# F030K6T6.net
KiCad netlist of a schematic drawn in Altium Designer
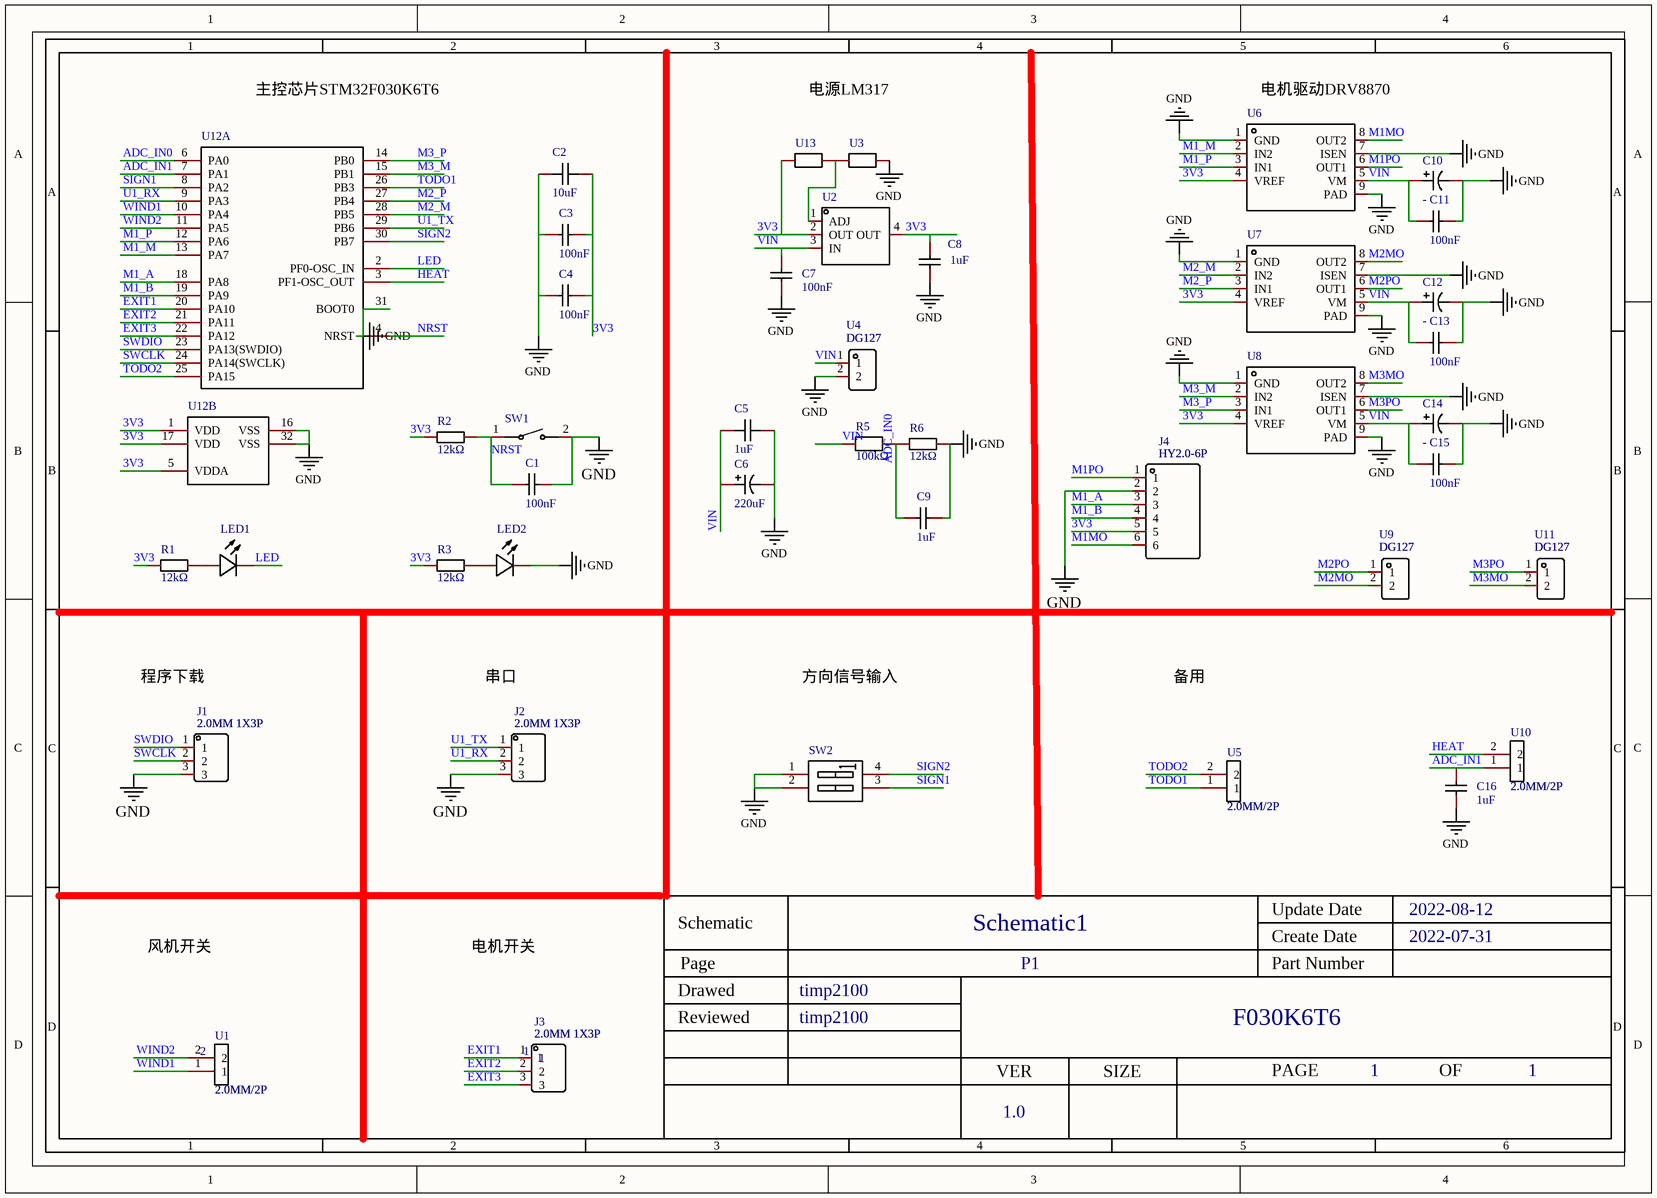
[diagram p0: F030K6T6.schdoc]

(export (version "E")
  (design (tool "Eeschema 10.0.6"))
  (components
    (comp (ref "C1")
      (value "100nF")
      (description "容值:100nF;精度:±20%;额定电压:50V;温度系数:Y5V;")
      (fields (field (name "MANUFACTURER") "FH(风华)") (field (name "MANUFACTURER PART") "0402F104M500NT"))
      (libsource (lib "altium-import") (part "root_0_0402F104M500NT_"))
    )
    (comp (ref "C2")
      (value "10uF")
      (description "容值:10uF;精度:±20%;额定电压:-;温度系数:-;")
      (fields
        (field (name "MANUFACTURER") "muRata(村田)")
        (field (name "MANUFACTURER PART") "GRJ155R60J106ME11D")
      )
      (libsource (lib "altium-import") (part "root_0_GRJ155R60J106ME11D_"))
    )
    (comp (ref "C3")
      (value "100nF")
      (description "容值:100nF;精度:±20%;额定电压:50V;温度系数:Y5V;")
      (fields (field (name "MANUFACTURER") "FH(风华)") (field (name "MANUFACTURER PART") "0402F104M500NT"))
      (libsource (lib "altium-import") (part "root_0_0402F104M500NT_"))
    )
    (comp (ref "C4")
      (value "100nF")
      (description "容值:100nF;精度:±20%;额定电压:50V;温度系数:Y5V;")
      (fields (field (name "MANUFACTURER") "FH(风华)") (field (name "MANUFACTURER PART") "0402F104M500NT"))
      (libsource (lib "altium-import") (part "root_0_0402F104M500NT_"))
    )
    (comp (ref "C5")
      (value "1uF")
      (description "容值:1uF;精度:±10%;额定电压:50V;温度系数:X5R;")
      (fields
        (field (name "MANUFACTURER") "muRata(村田)")
        (field (name "MANUFACTURER PART") "GRT188R61H105KE13D")
      )
      (libsource (lib "altium-import") (part "root_0_GRT188R61H105KE13D_"))
    )
    (comp (ref "C6")
      (value "220uF")
      (description "容值:220uF;额定电压:50V;工作寿命:2000hrs@105;")
      (fields
        (field (name "MANUFACTURER") "KNSCHA(科尼盛)")
        (field (name "MANUFACTURER PART") "RVT220UF50V67RV0021")
      )
      (libsource (lib "altium-import") (part "root_0_RVT220UF50V67RV0021_"))
    )
    (comp (ref "C7")
      (value "100nF")
      (description "容值:100nF;精度:±20%;额定电压:50V;温度系数:Y5V;")
      (fields (field (name "MANUFACTURER") "FH(风华)") (field (name "MANUFACTURER PART") "0402F104M500NT"))
      (libsource (lib "altium-import") (part "root_1_0402F104M500NT_"))
    )
    (comp (ref "C8")
      (value "1uF")
      (description "容值:1uF;精度:±10%;额定电压:10V;温度系数:X5R;")
      (fields
        (field (name "MANUFACTURER") "TAIYO YUDEN(太诱)")
        (field (name "MANUFACTURER PART") "LMK105BJ105KV-F")
      )
      (libsource (lib "altium-import") (part "root_1_LMK105BJ105KV-F_"))
    )
    (comp (ref "C9")
      (value "1uF")
      (description "容值:1uF;精度:±10%;额定电压:10V;温度系数:X5R;")
      (fields
        (field (name "MANUFACTURER") "TAIYO YUDEN(太诱)")
        (field (name "MANUFACTURER PART") "LMK105BJ105KV-F")
      )
      (libsource (lib "altium-import") (part "root_2_LMK105BJ105KV-F_"))
    )
    (comp (ref "C10")
      (value "-")
      (description "容值:-;精度:-;额定电压:-;电容体直径:-;电容体长度:-;纹波电流:-;等效串联电阻:-;工作寿命:-;工作温度:-;")
      (fields
        (field (name "MANUFACTURER") "KNSCHA(科尼盛)")
        (field (name "MANUFACTURER PART") "XT47UF50V90RV0082")
      )
      (libsource (lib "altium-import") (part "root_0_XT47UF50V90RV0082_"))
    )
    (comp (ref "C11")
      (value "100nF")
      (description "容值:100nF;精度:±20%;额定电压:50V;温度系数:Y5V;")
      (fields (field (name "MANUFACTURER") "FH(风华)") (field (name "MANUFACTURER PART") "0402F104M500NT"))
      (libsource (lib "altium-import") (part "root_0_0402F104M500NT_"))
    )
    (comp (ref "C12")
      (value "-")
      (description "容值:-;精度:-;额定电压:-;电容体直径:-;电容体长度:-;纹波电流:-;等效串联电阻:-;工作寿命:-;工作温度:-;")
      (fields
        (field (name "MANUFACTURER") "KNSCHA(科尼盛)")
        (field (name "MANUFACTURER PART") "XT47UF50V90RV0082")
      )
      (libsource (lib "altium-import") (part "root_0_XT47UF50V90RV0082_"))
    )
    (comp (ref "C13")
      (value "100nF")
      (description "容值:100nF;精度:±20%;额定电压:50V;温度系数:Y5V;")
      (fields (field (name "MANUFACTURER") "FH(风华)") (field (name "MANUFACTURER PART") "0402F104M500NT"))
      (libsource (lib "altium-import") (part "root_0_0402F104M500NT_"))
    )
    (comp (ref "C14")
      (value "-")
      (description "容值:-;精度:-;额定电压:-;电容体直径:-;电容体长度:-;纹波电流:-;等效串联电阻:-;工作寿命:-;工作温度:-;")
      (fields
        (field (name "MANUFACTURER") "KNSCHA(科尼盛)")
        (field (name "MANUFACTURER PART") "XT47UF50V90RV0082")
      )
      (libsource (lib "altium-import") (part "root_0_XT47UF50V90RV0082_"))
    )
    (comp (ref "C15")
      (value "100nF")
      (description "容值:100nF;精度:±20%;额定电压:50V;温度系数:Y5V;")
      (fields (field (name "MANUFACTURER") "FH(风华)") (field (name "MANUFACTURER PART") "0402F104M500NT"))
      (libsource (lib "altium-import") (part "root_0_0402F104M500NT_"))
    )
    (comp (ref "C16")
      (value "1uF")
      (description "容值:1uF;精度:±10%;额定电压:10V;温度系数:X5R;")
      (fields
        (field (name "MANUFACTURER") "TAIYO YUDEN(太诱)")
        (field (name "MANUFACTURER PART") "LMK105BJ105KV-F")
      )
      (libsource (lib "altium-import") (part "root_3_LMK105BJ105KV-F_"))
    )
    (comp (ref "J1")
      (value "2.0MM 1X3P")
      (fields (field (name "NAME") "2.0MM 1X3P"))
      (libsource (lib "altium-import") (part "root_0_2.0MM 1X3P_"))
    )
    (comp (ref "J2")
      (value "2.0MM 1X3P")
      (fields (field (name "NAME") "2.0MM 1X3P"))
      (libsource (lib "altium-import") (part "root_0_2.0MM 1X3P_"))
    )
    (comp (ref "J3")
      (value "2.0MM 1X3P")
      (fields (field (name "NAME") "2.0MM 1X3P") (field (name "NAME_1") "1") (field (name "NUMBER") "1"))
      (libsource (lib "altium-import") (part "root_0_2.0MM 1X3P_"))
    )
    (comp (ref "J4")
      (value "HY2.0-6P")
      (fields (field (name "NAME") "HY2.0-6P"))
      (libsource (lib "altium-import") (part "root_0_HY2.0-6P_"))
    )
    (comp (ref "LED1")
      (value "MHT136CRCT")
      (fields (field (name "MANUFACTURER") "MEIHUA(美华科技)"))
      (libsource (lib "altium-import") (part "root_0_mirrored_MHT136CRCT_"))
    )
    (comp (ref "LED2")
      (value "MHT136CGCT")
      (fields (field (name "MANUFACTURER") "MEIHUA(美华科技)"))
      (libsource (lib "altium-import") (part "root_0_mirrored_MHT136CGCT_"))
    )
    (comp (ref "R1")
      (value "12kΩ")
      (description "电阻类型:厚膜电阻;阻值:12kΩ;精度:±5%;功率:1/16W;温度系数:±100ppm/;最大工作电压:50V;工作温度范围:-55~+155;")
      (fields
        (field (name "MANUFACTURER") "UNI-ROYAL(厚声)")
        (field (name "MANUFACTURER PART") "0402WGJ0123TCE")
      )
      (libsource (lib "altium-import") (part "root_0_0402WGJ0123TCE_"))
    )
    (comp (ref "R2")
      (value "12kΩ")
      (description "电阻类型:厚膜电阻;阻值:12kΩ;精度:±5%;功率:1/16W;温度系数:±100ppm/;最大工作电压:50V;工作温度范围:-55~+155;")
      (fields
        (field (name "MANUFACTURER") "UNI-ROYAL(厚声)")
        (field (name "MANUFACTURER PART") "0402WGJ0123TCE")
      )
      (libsource (lib "altium-import") (part "root_0_0402WGJ0123TCE_"))
    )
    (comp (ref "R3")
      (value "12kΩ")
      (description "电阻类型:厚膜电阻;阻值:12kΩ;精度:±5%;功率:1/16W;温度系数:±100ppm/;最大工作电压:50V;工作温度范围:-55~+155;")
      (fields
        (field (name "MANUFACTURER") "UNI-ROYAL(厚声)")
        (field (name "MANUFACTURER PART") "0402WGJ0123TCE")
      )
      (libsource (lib "altium-import") (part "root_0_0402WGJ0123TCE_"))
    )
    (comp (ref "R5")
      (value "100kΩ")
      (description "电阻类型:薄膜电阻;阻值:100kΩ;精度:±0.25%;功率:62.5mW;温度系数:±50ppm/;最大工作电压:50V;工作温度范围:-55~+155;")
      (fields (field (name "MANUFACTURER") "YAGEO(国巨)") (field (name "MANUFACTURER PART") "RT0402CRE07100KL"))
      (libsource (lib "altium-import") (part "root_0_RT0402CRE07100KL_"))
    )
    (comp (ref "R6")
      (value "12kΩ")
      (description "电阻类型:厚膜电阻;阻值:12kΩ;精度:±5%;功率:1/16W;温度系数:±100ppm/;最大工作电压:50V;工作温度范围:-55~+155;")
      (fields
        (field (name "MANUFACTURER") "UNI-ROYAL(厚声)")
        (field (name "MANUFACTURER PART") "0402WGJ0123TCE")
      )
      (libsource (lib "altium-import") (part "root_0_0402WGJ0123TCE_"))
    )
    (comp (ref "SW1")
      (value "K2-1107ST-A4DW-06")
      (fields (field (name "MANUFACTURER") "韩国韩荣"))
      (libsource (lib "altium-import") (part "root_0_K2-1107ST-A4DW-06_"))
    )
    (comp (ref "SW2")
      (value "DS-02RP")
      (description "类型:平拨，凸起式;额定电流:25mA;额定电压:24V;电路结构:单刀单掷;开关位数:2;引脚间距:2.54mm;工作温度:-20~+70;使用寿命:3000;颜色:红色;")
      (fields (field (name "MANUFACTURER") "韩国韩荣"))
      (libsource (lib "altium-import") (part "root_0_DS-02RP_"))
    )
    (comp (ref "U1")
      (value "2.0MM/2P")
      (fields (field (name "NAME") "2.0MM/2P") (field (name "NUMBER") "2"))
      (libsource (lib "altium-import") (part "root_0_mirrored_2.0MM/2P_"))
    )
    (comp (ref "U2")
      (value "LM317")
      (description "输出类型:可调;输出极性:正;输出通道数:1;最大输入电压:40V;输出电压:1.2V~37V;压差:5V@(500mA);输出电流:1.5A;")
      (fields (field (name "MANUFACTURER") "CJ（江苏长电/长晶）"))
      (libsource (lib "altium-import") (part "root_0_LM317_"))
    )
    (comp (ref "U3")
      (value "SCR0402J20K")
      (fields (field (name "MANUFACTURER") "VO(翔胜)"))
      (libsource (lib "altium-import") (part "root_0_SCR0402J20K_"))
    )
    (comp (ref "U4")
      (value "DG127")
      (fields
        (field (name "NAME") "DG127")
        (field (name "MANUFACTURER") "DEGSON")
        (field (name "MANUFACTURER PART") "DG127-5.0-02P-14-1002A(H)")
      )
      (libsource (lib "altium-import") (part "root_0_DG127-5.0-02P-14-1002A(H)_"))
    )
    (comp (ref "U5")
      (value "2.0MM/2P")
      (fields (field (name "NAME") "2.0MM/2P"))
      (libsource (lib "altium-import") (part "root_0_mirrored_2.0MM/2P_"))
    )
    (comp (ref "U6")
      (value "DRV8870DDAR")
      (description "DRV8870 DRV8870 预售")
      (fields (field (name "MANUFACTURER") "TI(德州仪器)"))
      (libsource (lib "altium-import") (part "root_0_DRV8870DDAR_"))
    )
    (comp (ref "U7")
      (value "DRV8870DDAR")
      (description "DRV8870 DRV8870 预售")
      (fields (field (name "MANUFACTURER") "TI(德州仪器)"))
      (libsource (lib "altium-import") (part "root_0_DRV8870DDAR_"))
    )
    (comp (ref "U8")
      (value "DRV8870DDAR")
      (description "DRV8870 DRV8870 预售")
      (fields (field (name "MANUFACTURER") "TI(德州仪器)"))
      (libsource (lib "altium-import") (part "root_0_DRV8870DDAR_"))
    )
    (comp (ref "U9")
      (value "DG127")
      (fields
        (field (name "NAME") "DG127")
        (field (name "MANUFACTURER") "DEGSON")
        (field (name "MANUFACTURER PART") "DG127-5.0-02P-14-1002A(H)")
      )
      (libsource (lib "altium-import") (part "root_0_DG127-5.0-02P-14-1002A(H)_"))
    )
    (comp (ref "U10")
      (value "2.0MM/2P")
      (fields (field (name "NAME") "2.0MM/2P"))
      (libsource (lib "altium-import") (part "root_0_mirrored_2.0MM/2P_"))
    )
    (comp (ref "U11")
      (value "DG127")
      (fields
        (field (name "NAME") "DG127")
        (field (name "MANUFACTURER") "DEGSON")
        (field (name "MANUFACTURER PART") "DG127-5.0-02P-14-1002A(H)")
      )
      (libsource (lib "altium-import") (part "root_0_DG127-5.0-02P-14-1002A(H)_"))
    )
    (comp (ref "U12")
      (value "STM32F030K6T6TR")
      (description "CPU位数:-;ROM类型:-;CPU内核:-;主频（MAX):-;工作电压:-;")
      (fields (field (name "MANUFACTURER") "ST(意法半导体)"))
      (libsource (lib "altium-import") (part "root_0_STM32F030K6T6TR_"))
    )
    (comp (ref "U13")
      (value "SCR0402J20K")
      (fields (field (name "MANUFACTURER") "VO(翔胜)"))
      (libsource (lib "altium-import") (part "root_0_SCR0402J20K_"))
    )
  )
  (nets
    (net (code "1") (name "/3V3") (class "Default")
      (node (ref "C2") (pin "2") (pinfunction "2_2") (pintype "passive"))
      (node (ref "C3") (pin "2") (pinfunction "2_2") (pintype "passive"))
      (node (ref "C4") (pin "2") (pinfunction "2_2") (pintype "passive"))
      (node (ref "C8") (pin "2") (pinfunction "2_2") (pintype "passive"))
      (node (ref "J4") (pin "5") (pinfunction "5_5") (pintype "passive"))
      (node (ref "R1") (pin "1") (pinfunction "1_1") (pintype "passive"))
      (node (ref "R2") (pin "1") (pinfunction "1_1") (pintype "passive"))
      (node (ref "R3") (pin "1") (pinfunction "1_1") (pintype "passive"))
      (node (ref "U12") (pin "1") (pinfunction "VDD_1") (pintype "passive"))
      (node (ref "U12") (pin "17") (pinfunction "VDD_17") (pintype "passive"))
      (node (ref "U12") (pin "5") (pinfunction "VDDA_5") (pintype "passive"))
      (node (ref "U13") (pin "1") (pinfunction "1_1") (pintype "passive"))
      (node (ref "U2") (pin "2") (pinfunction "OUT_2") (pintype "passive"))
      (node (ref "U2") (pin "4") (pinfunction "OUT_4") (pintype "passive"))
      (node (ref "U6") (pin "4") (pinfunction "VREF_4") (pintype "passive"))
      (node (ref "U7") (pin "4") (pinfunction "VREF_4") (pintype "passive"))
      (node (ref "U8") (pin "4") (pinfunction "VREF_4") (pintype "passive"))
    )
    (net (code "2") (name "/ADC_IN0") (class "Default")
      (node (ref "C9") (pin "2") (pinfunction "2_2") (pintype "passive"))
      (node (ref "R5") (pin "2") (pinfunction "2_2") (pintype "passive"))
      (node (ref "R6") (pin "1") (pinfunction "1_1") (pintype "passive"))
      (node (ref "U12") (pin "6") (pinfunction "PA0_6") (pintype "passive"))
    )
    (net (code "3") (name "/ADC_IN1") (class "Default")
      (node (ref "C16") (pin "1") (pinfunction "1_1") (pintype "passive"))
      (node (ref "U10") (pin "1") (pinfunction "1_1") (pintype "passive"))
      (node (ref "U12") (pin "7") (pinfunction "PA1_7") (pintype "passive"))
    )
    (net (code "4") (name "/EXIT1") (class "Default")
      (node (ref "J3") (pin "1") (pinfunction "1_1") (pintype "passive"))
      (node (ref "U12") (pin "20") (pinfunction "PA10_20") (pintype "passive"))
    )
    (net (code "5") (name "/EXIT2") (class "Default")
      (node (ref "J3") (pin "2") (pinfunction "2_2") (pintype "passive"))
      (node (ref "U12") (pin "21") (pinfunction "PA11_21") (pintype "passive"))
    )
    (net (code "6") (name "/EXIT3") (class "Default")
      (node (ref "J3") (pin "3") (pinfunction "3_3") (pintype "passive"))
      (node (ref "U12") (pin "22") (pinfunction "PA12_22") (pintype "passive"))
    )
    (net (code "7") (name "/HEAT") (class "Default")
      (node (ref "U10") (pin "2") (pinfunction "2_2") (pintype "passive"))
      (node (ref "U12") (pin "3") (pinfunction "PF1-OSC_OUT_3") (pintype "passive"))
    )
    (net (code "8") (name "/LED") (class "Default")
      (node (ref "LED1") (pin "1") (pinfunction "K_1") (pintype "passive"))
      (node (ref "U12") (pin "2") (pinfunction "PF0-OSC_IN_2") (pintype "passive"))
    )
    (net (code "9") (name "/M1MO") (class "Default")
      (node (ref "J4") (pin "6") (pinfunction "6_6") (pintype "passive"))
      (node (ref "U6") (pin "8") (pinfunction "OUT2_8") (pintype "passive"))
    )
    (net (code "10") (name "/M1PO") (class "Default")
      (node (ref "J4") (pin "1") (pinfunction "1_1") (pintype "passive"))
      (node (ref "U6") (pin "6") (pinfunction "OUT1_6") (pintype "passive"))
    )
    (net (code "11") (name "/M1_A") (class "Default")
      (node (ref "J4") (pin "3") (pinfunction "3_3") (pintype "passive"))
      (node (ref "U12") (pin "18") (pinfunction "PA8_18") (pintype "passive"))
    )
    (net (code "12") (name "/M1_B") (class "Default")
      (node (ref "J4") (pin "4") (pinfunction "4_4") (pintype "passive"))
      (node (ref "U12") (pin "19") (pinfunction "PA9_19") (pintype "passive"))
    )
    (net (code "13") (name "/M1_M") (class "Default")
      (node (ref "U12") (pin "13") (pinfunction "PA7_13") (pintype "passive"))
      (node (ref "U6") (pin "2") (pinfunction "IN2_2") (pintype "passive"))
    )
    (net (code "14") (name "/M1_P") (class "Default")
      (node (ref "U12") (pin "12") (pinfunction "PA6_12") (pintype "passive"))
      (node (ref "U6") (pin "3") (pinfunction "IN1_3") (pintype "passive"))
    )
    (net (code "15") (name "/M2MO") (class "Default")
      (node (ref "U7") (pin "8") (pinfunction "OUT2_8") (pintype "passive"))
      (node (ref "U9") (pin "2") (pinfunction "2_2") (pintype "passive"))
    )
    (net (code "16") (name "/M2PO") (class "Default")
      (node (ref "U7") (pin "6") (pinfunction "OUT1_6") (pintype "passive"))
      (node (ref "U9") (pin "1") (pinfunction "1_1") (pintype "passive"))
    )
    (net (code "17") (name "/M2_M") (class "Default")
      (node (ref "U12") (pin "28") (pinfunction "PB5_28") (pintype "passive"))
      (node (ref "U7") (pin "2") (pinfunction "IN2_2") (pintype "passive"))
    )
    (net (code "18") (name "/M2_P") (class "Default")
      (node (ref "U12") (pin "27") (pinfunction "PB4_27") (pintype "passive"))
      (node (ref "U7") (pin "3") (pinfunction "IN1_3") (pintype "passive"))
    )
    (net (code "19") (name "/M3MO") (class "Default")
      (node (ref "U11") (pin "2") (pinfunction "2_2") (pintype "passive"))
      (node (ref "U8") (pin "8") (pinfunction "OUT2_8") (pintype "passive"))
    )
    (net (code "20") (name "/M3PO") (class "Default")
      (node (ref "U11") (pin "1") (pinfunction "1_1") (pintype "passive"))
      (node (ref "U8") (pin "6") (pinfunction "OUT1_6") (pintype "passive"))
    )
    (net (code "21") (name "/M3_M") (class "Default")
      (node (ref "U12") (pin "15") (pinfunction "PB1_15") (pintype "passive"))
      (node (ref "U8") (pin "2") (pinfunction "IN2_2") (pintype "passive"))
    )
    (net (code "22") (name "/M3_P") (class "Default")
      (node (ref "U12") (pin "14") (pinfunction "PB0_14") (pintype "passive"))
      (node (ref "U8") (pin "3") (pinfunction "IN1_3") (pintype "passive"))
    )
    (net (code "23") (name "/NRST") (class "Default")
      (node (ref "C1") (pin "1") (pinfunction "1_1") (pintype "passive"))
      (node (ref "R2") (pin "2") (pinfunction "2_2") (pintype "passive"))
      (node (ref "SW1") (pin "1") (pinfunction "1_1") (pintype "passive"))
      (node (ref "U12") (pin "4") (pinfunction "NRST_4") (pintype "passive"))
    )
    (net (code "24") (name "/SIGN1") (class "Default")
      (node (ref "SW2") (pin "3") (pinfunction "3_3") (pintype "passive"))
      (node (ref "U12") (pin "8") (pinfunction "PA2_8") (pintype "passive"))
    )
    (net (code "25") (name "/SIGN2") (class "Default")
      (node (ref "SW2") (pin "4") (pinfunction "4_4") (pintype "passive"))
      (node (ref "U12") (pin "30") (pinfunction "PB7_30") (pintype "passive"))
    )
    (net (code "26") (name "/SWCLK") (class "Default")
      (node (ref "J1") (pin "2") (pinfunction "2_2") (pintype "passive"))
      (node (ref "U12") (pin "24") (pinfunction "PA14(SWCLK)_24") (pintype "passive"))
    )
    (net (code "27") (name "/SWDIO") (class "Default")
      (node (ref "J1") (pin "1") (pinfunction "1_1") (pintype "passive"))
      (node (ref "U12") (pin "23") (pinfunction "PA13(SWDIO)_23") (pintype "passive"))
    )
    (net (code "28") (name "/TODO1") (class "Default")
      (node (ref "U12") (pin "26") (pinfunction "PB3_26") (pintype "passive"))
      (node (ref "U5") (pin "1") (pinfunction "1_1") (pintype "passive"))
    )
    (net (code "29") (name "/TODO2") (class "Default")
      (node (ref "U12") (pin "25") (pinfunction "PA15_25") (pintype "passive"))
      (node (ref "U5") (pin "2") (pinfunction "2_2") (pintype "passive"))
    )
    (net (code "30") (name "/U1_RX") (class "Default")
      (node (ref "J2") (pin "2") (pinfunction "2_2") (pintype "passive"))
      (node (ref "U12") (pin "9") (pinfunction "PA3_9") (pintype "passive"))
    )
    (net (code "31") (name "/U1_TX") (class "Default")
      (node (ref "J2") (pin "1") (pinfunction "1_1") (pintype "passive"))
      (node (ref "U12") (pin "29") (pinfunction "PB6_29") (pintype "passive"))
    )
    (net (code "32") (name "/VIN") (class "Default")
      (node (ref "C10") (pin "1") (pinfunction "1_1") (pintype "passive"))
      (node (ref "C11") (pin "1") (pinfunction "1_1") (pintype "passive"))
      (node (ref "C12") (pin "1") (pinfunction "1_1") (pintype "passive"))
      (node (ref "C13") (pin "1") (pinfunction "1_1") (pintype "passive"))
      (node (ref "C14") (pin "1") (pinfunction "1_1") (pintype "passive"))
      (node (ref "C15") (pin "1") (pinfunction "1_1") (pintype "passive"))
      (node (ref "C5") (pin "2") (pinfunction "2_2") (pintype "passive"))
      (node (ref "C6") (pin "1") (pinfunction "1_1") (pintype "passive"))
      (node (ref "C7") (pin "2") (pinfunction "2_2") (pintype "passive"))
      (node (ref "R5") (pin "1") (pinfunction "1_1") (pintype "passive"))
      (node (ref "U2") (pin "3") (pinfunction "IN_3") (pintype "passive"))
      (node (ref "U4") (pin "1") (pinfunction "1_1") (pintype "passive"))
      (node (ref "U6") (pin "5") (pinfunction "VM_5") (pintype "passive"))
      (node (ref "U7") (pin "5") (pinfunction "VM_5") (pintype "passive"))
      (node (ref "U8") (pin "5") (pinfunction "VM_5") (pintype "passive"))
    )
    (net (code "33") (name "/WIND1") (class "Default")
      (node (ref "U1") (pin "1") (pinfunction "1_1") (pintype "passive"))
      (node (ref "U12") (pin "10") (pinfunction "PA4_10") (pintype "passive"))
    )
    (net (code "34") (name "/WIND2") (class "Default")
      (node (ref "U1") (pin "2") (pinfunction "2_2") (pintype "passive"))
      (node (ref "U12") (pin "11") (pinfunction "PA5_11") (pintype "passive"))
    )
    (net (code "35") (name "GND") (class "Default")
      (node (ref "C1") (pin "2") (pinfunction "2_2") (pintype "passive"))
      (node (ref "C10") (pin "2") (pinfunction "2_2") (pintype "passive"))
      (node (ref "C11") (pin "2") (pinfunction "2_2") (pintype "passive"))
      (node (ref "C12") (pin "2") (pinfunction "2_2") (pintype "passive"))
      (node (ref "C13") (pin "2") (pinfunction "2_2") (pintype "passive"))
      (node (ref "C14") (pin "2") (pinfunction "2_2") (pintype "passive"))
      (node (ref "C15") (pin "2") (pinfunction "2_2") (pintype "passive"))
      (node (ref "C16") (pin "2") (pinfunction "2_2") (pintype "passive"))
      (node (ref "C2") (pin "1") (pinfunction "1_1") (pintype "passive"))
      (node (ref "C3") (pin "1") (pinfunction "1_1") (pintype "passive"))
      (node (ref "C4") (pin "1") (pinfunction "1_1") (pintype "passive"))
      (node (ref "C5") (pin "1") (pinfunction "1_1") (pintype "passive"))
      (node (ref "C6") (pin "2") (pinfunction "2_2") (pintype "passive"))
      (node (ref "C7") (pin "1") (pinfunction "1_1") (pintype "passive"))
      (node (ref "C8") (pin "1") (pinfunction "1_1") (pintype "passive"))
      (node (ref "C9") (pin "1") (pinfunction "1_1") (pintype "passive"))
      (node (ref "J1") (pin "3") (pinfunction "3_3") (pintype "passive"))
      (node (ref "J2") (pin "3") (pinfunction "3_3") (pintype "passive"))
      (node (ref "J4") (pin "2") (pinfunction "2_2") (pintype "passive"))
      (node (ref "LED2") (pin "1") (pinfunction "K_1") (pintype "passive"))
      (node (ref "R6") (pin "2") (pinfunction "2_2") (pintype "passive"))
      (node (ref "SW1") (pin "2") (pinfunction "2_2") (pintype "passive"))
      (node (ref "SW2") (pin "1") (pinfunction "A1_1") (pintype "passive"))
      (node (ref "SW2") (pin "2") (pinfunction "A2_2") (pintype "passive"))
      (node (ref "U12") (pin "16") (pinfunction "VSS_16") (pintype "passive"))
      (node (ref "U12") (pin "31") (pinfunction "BOOT0_31") (pintype "passive"))
      (node (ref "U12") (pin "32") (pinfunction "VSS_32") (pintype "passive"))
      (node (ref "U3") (pin "2") (pinfunction "2_2") (pintype "passive"))
      (node (ref "U4") (pin "2") (pinfunction "2_2") (pintype "passive"))
      (node (ref "U6") (pin "1") (pinfunction "GND_1") (pintype "passive"))
      (node (ref "U6") (pin "7") (pinfunction "ISEN_7") (pintype "passive"))
      (node (ref "U6") (pin "9") (pinfunction "PAD_9") (pintype "passive"))
      (node (ref "U7") (pin "1") (pinfunction "GND_1") (pintype "passive"))
      (node (ref "U7") (pin "7") (pinfunction "ISEN_7") (pintype "passive"))
      (node (ref "U7") (pin "9") (pinfunction "PAD_9") (pintype "passive"))
      (node (ref "U8") (pin "1") (pinfunction "GND_1") (pintype "passive"))
      (node (ref "U8") (pin "7") (pinfunction "ISEN_7") (pintype "passive"))
      (node (ref "U8") (pin "9") (pinfunction "PAD_9") (pintype "passive"))
    )
    (net (code "36") (name "Net-(LED1-A)") (class "Default")
      (node (ref "LED1") (pin "2") (pinfunction "A_2") (pintype "passive"))
      (node (ref "R1") (pin "2") (pinfunction "2_2") (pintype "passive"))
    )
    (net (code "37") (name "Net-(LED2-A)") (class "Default")
      (node (ref "LED2") (pin "2") (pinfunction "A_2") (pintype "passive"))
      (node (ref "R3") (pin "2") (pinfunction "2_2") (pintype "passive"))
    )
    (net (code "38") (name "Net-(U2-ADJ)") (class "Default")
      (node (ref "U13") (pin "2") (pinfunction "2_2") (pintype "passive"))
      (node (ref "U2") (pin "1") (pinfunction "ADJ_1") (pintype "passive"))
      (node (ref "U3") (pin "1") (pinfunction "1_1") (pintype "passive"))
    )
  )
)
